# DM1097_HDMI.net
KiCad netlist of a schematic drawn in Altium Designer
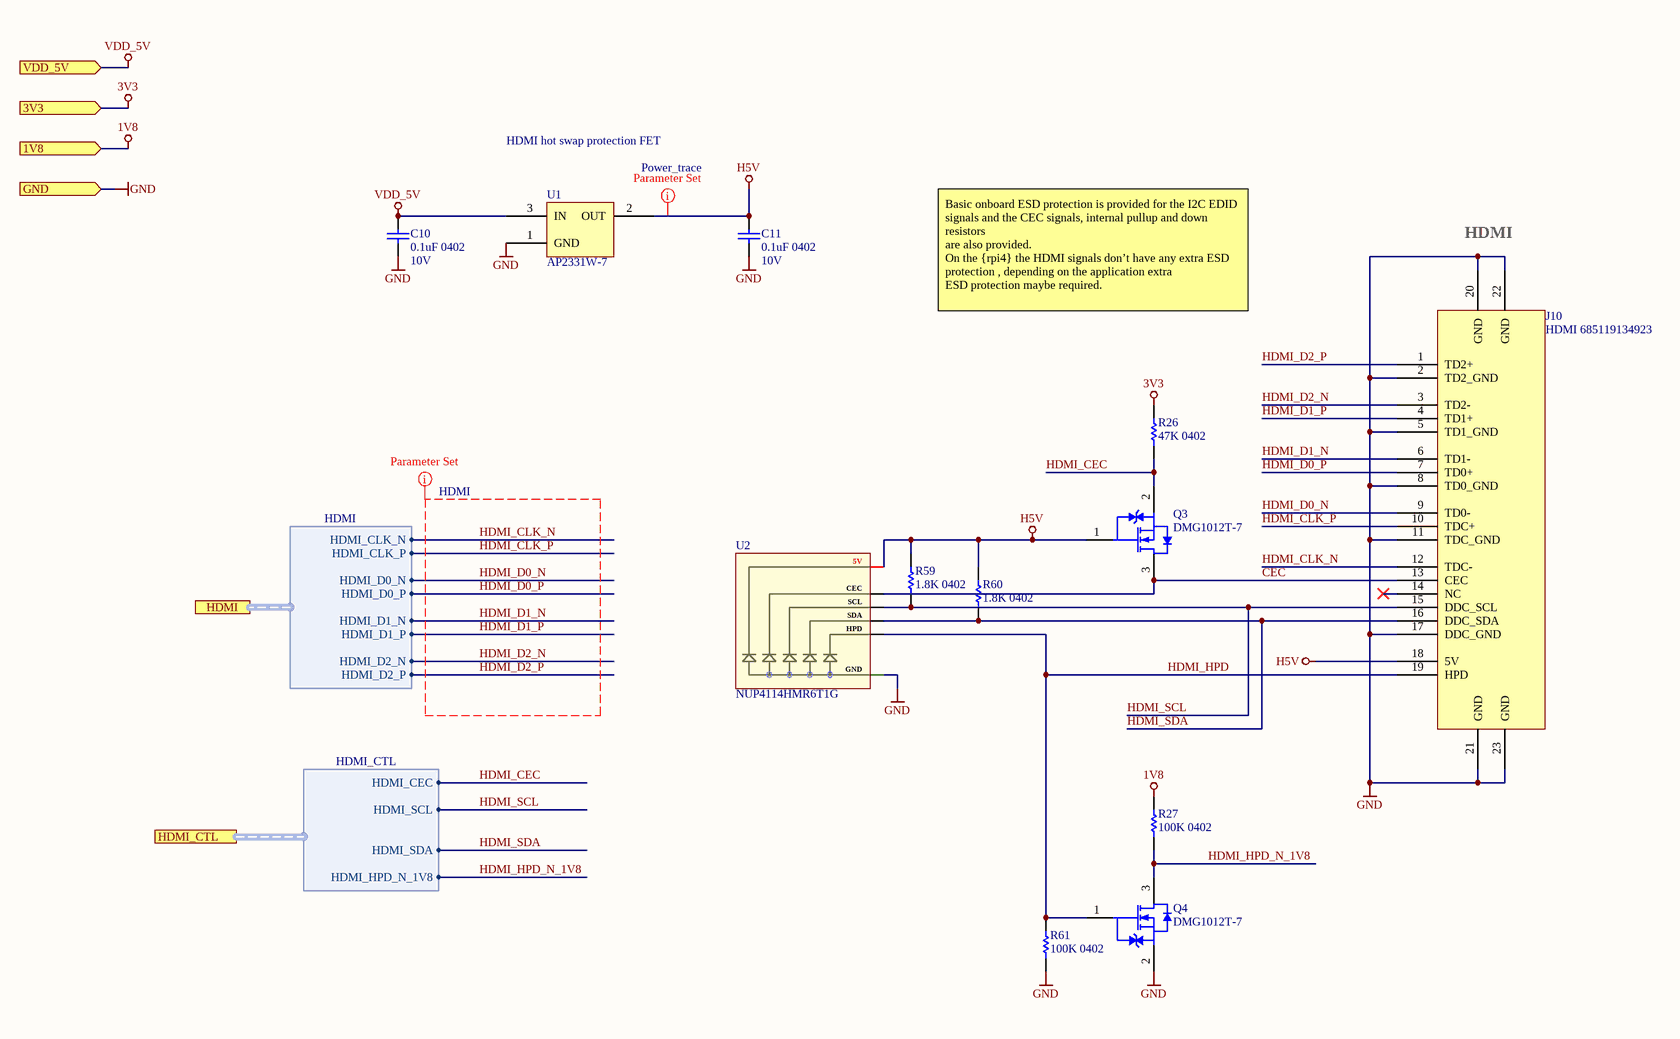
[diagram p0: DM1097_HDMI.SchDoc]

(export (version "E")
  (design (tool "Eeschema 10.0.6"))
  (components
    (comp (ref "C10")
      (value "0.1uF 0402")
      (footprint "CAP_Altium_Vault_Generic:CAPC0402(1005)70_N")
      (description "CAP CER 0.1UF 10V X7R 0402 5%")
      (fields (field (name "TOLERANCE") "5%") (field (name "VOLTAGE RATING") "10V"))
      (libsource (lib "LuxonisMaster") (part "GRM155R71A104JA01D"))
    )
    (comp (ref "C11")
      (value "0.1uF 0402")
      (footprint "CAP_Altium_Vault_Generic:CAPC0402(1005)70_N")
      (description "CAP CER 0.1UF 10V X7R 0402 5%")
      (fields (field (name "TOLERANCE") "5%") (field (name "VOLTAGE RATING") "10V"))
      (libsource (lib "LuxonisMaster") (part "GRM155R71A104JA01D"))
    )
    (comp (ref "J10")
      (value "HDMI 685119134923")
      (footprint "LuxonisMaster:685119134923")
      (description "CONN RCPT HDMI 19POS SMD R/A")
      (libsource (lib "LuxonisMaster") (part "685119134923"))
    )
    (comp (ref "Q3")
      (value "DMG1012T-7")
      (footprint "LuxonisMaster:DMG1012T-7")
      (description "MOSFET N-CH 20V 630MA SOT-523")
      (libsource (lib "LuxonisMaster") (part "DMG1012T-7"))
    )
    (comp (ref "Q4")
      (value "DMG1012T-7")
      (footprint "LuxonisMaster:DMG1012T-7")
      (description "MOSFET N-CH 20V 630MA SOT-523")
      (libsource (lib "LuxonisMaster") (part "DMG1012T-7"))
    )
    (comp (ref "R26")
      (value "47K 0402")
      (footprint "RES_Altium_Vault_Generic:RESC0402(1005)_N")
      (description "RES SMD 47K OHM 1% 1/16W 0402")
      (fields (field (name "TOLERANCE") "1%"))
      (libsource (lib "LuxonisMaster") (part "RC0402FR-0747KL"))
    )
    (comp (ref "R27")
      (value "100K 0402")
      (footprint "RES_Altium_Vault_Generic:RESC0402(1005)_N")
      (description "RES SMD 100K OHM 1% 1/16W 0402")
      (fields (field (name "TOLERANCE") "1%"))
      (libsource (lib "LuxonisMaster") (part "RC0402FR-07100KL"))
    )
    (comp (ref "R59")
      (value "1.8K 0402")
      (footprint "RES_Altium_Vault_Generic:RESC0402(1005)_L")
      (description "RES SMD 1.8K OHM 1% 1/16W 0402")
      (fields (field (name "TOLERANCE") "1%"))
      (libsource (lib "LuxonisMaster") (part "RC0402FR-071K8L"))
    )
    (comp (ref "R60")
      (value "1.8K 0402")
      (footprint "RES_Altium_Vault_Generic:RESC0402(1005)_L")
      (description "RES SMD 1.8K OHM 1% 1/16W 0402")
      (fields (field (name "TOLERANCE") "1%"))
      (libsource (lib "LuxonisMaster") (part "RC0402FR-071K8L"))
    )
    (comp (ref "R61")
      (value "100K 0402")
      (footprint "RES_Altium_Vault_Generic:RESC0402(1005)_N")
      (description "RES SMD 47K OHM 1% 1/16W 0402")
      (fields (field (name "TOLERANCE") "1%"))
      (libsource (lib "LuxonisMaster") (part "RC0402FR-0747KL"))
    )
    (comp (ref "U1")
      (value "AP2331W-7")
      (footprint "LuxonisMaster:AP2331W-7")
      (description "LOAD SWITCH SC59")
      (fields (field (name "VOLTAGE") "5.2V"))
      (libsource (lib "LuxonisMaster") (part "AP2331W-7"))
    )
    (comp (ref "U2")
      (value "NUP4114HMR6T1G")
      (footprint "SOT23-6")
      (description "TVS DIODE 3VWM 9WLCSP")
      (libsource (lib "DM1097_SchLib") (part "NUP4114"))
    )
  )
  (nets
    (net (code "3") (name "/CEC") (class "Default")
      (node (ref "J10") (pin "13") (pinfunction "CEC_13") (pintype "passive"))
      (node (ref "Q3") (pin "3") (pinfunction "3_3") (pintype "passive"))
      (node (ref "U2") (pin "1") (pinfunction "A2_1") (pintype "passive"))
    )
    (net (code "4") (name "/HDMI_CEC") (class "Default")
      (node (ref "Q3") (pin "2") (pinfunction "2_2") (pintype "passive"))
      (node (ref "R26") (pin "1") (pinfunction "1_1") (pintype "passive"))
    )
    (net (code "5") (name "/HDMI_CLK_N") (class "Default")
      (node (ref "J10") (pin "12") (pinfunction "TDC-_12") (pintype "passive"))
    )
    (net (code "6") (name "/HDMI_CLK_P") (class "Default")
      (node (ref "J10") (pin "10") (pinfunction "TDC+_10") (pintype "passive"))
    )
    (net (code "7") (name "/HDMI_D0_N") (class "Default")
      (node (ref "J10") (pin "9") (pinfunction "TD0-_9") (pintype "passive"))
    )
    (net (code "8") (name "/HDMI_D0_P") (class "Default")
      (node (ref "J10") (pin "7") (pinfunction "TD0+_7") (pintype "passive"))
    )
    (net (code "9") (name "/HDMI_D1_N") (class "Default")
      (node (ref "J10") (pin "6") (pinfunction "TD1-_6") (pintype "passive"))
    )
    (net (code "10") (name "/HDMI_D1_P") (class "Default")
      (node (ref "J10") (pin "4") (pinfunction "TD1+_4") (pintype "passive"))
    )
    (net (code "11") (name "/HDMI_D2_N") (class "Default")
      (node (ref "J10") (pin "3") (pinfunction "TD2-_3") (pintype "passive"))
    )
    (net (code "12") (name "/HDMI_D2_P") (class "Default")
      (node (ref "J10") (pin "1") (pinfunction "TD2+_1") (pintype "passive"))
    )
    (net (code "13") (name "/HDMI_HPD") (class "Default")
      (node (ref "J10") (pin "19") (pinfunction "HPD_19") (pintype "passive"))
      (node (ref "Q4") (pin "1") (pinfunction "1_1") (pintype "passive"))
      (node (ref "R61") (pin "2") (pinfunction "2_2") (pintype "passive"))
      (node (ref "U2") (pin "6") (pinfunction "1_6") (pintype "passive"))
    )
    (net (code "14") (name "/HDMI_HPD_N_1V8") (class "Default")
      (node (ref "Q4") (pin "3") (pinfunction "3_3") (pintype "passive"))
      (node (ref "R27") (pin "1") (pinfunction "1_1") (pintype "passive"))
    )
    (net (code "15") (name "/HDMI_SCL") (class "Default")
      (node (ref "J10") (pin "15") (pinfunction "DDC_SCL_15") (pintype "passive"))
      (node (ref "R59") (pin "1") (pinfunction "1_1") (pintype "passive"))
      (node (ref "U2") (pin "3") (pinfunction "A3_3") (pintype "passive"))
    )
    (net (code "16") (name "/HDMI_SDA") (class "Default")
      (node (ref "J10") (pin "16") (pinfunction "DDC_SDA_16") (pintype "passive"))
      (node (ref "R60") (pin "1") (pinfunction "1_1") (pintype "passive"))
      (node (ref "U2") (pin "4") (pinfunction "B3_4") (pintype "passive"))
    )
    (net (code "19") (name "1V8") (class "Default")
      (node (ref "R27") (pin "2") (pinfunction "2_2") (pintype "passive"))
    )
    (net (code "20") (name "3V3") (class "Default")
      (node (ref "R26") (pin "2") (pinfunction "2_2") (pintype "passive"))
    )
    (net (code "21") (name "GND") (class "Default")
      (node (ref "C10") (pin "1") (pinfunction "1_1") (pintype "passive"))
      (node (ref "C11") (pin "1") (pinfunction "1_1") (pintype "passive"))
      (node (ref "J10") (pin "11") (pinfunction "TDC_GND_11") (pintype "passive"))
      (node (ref "J10") (pin "17") (pinfunction "DDC_GND_17") (pintype "passive"))
      (node (ref "J10") (pin "2") (pinfunction "TD2_GND_2") (pintype "passive"))
      (node (ref "J10") (pin "20") (pinfunction "GND_20") (pintype "passive"))
      (node (ref "J10") (pin "21") (pinfunction "GND_21") (pintype "passive"))
      (node (ref "J10") (pin "22") (pinfunction "GND_22") (pintype "passive"))
      (node (ref "J10") (pin "23") (pinfunction "GND_23") (pintype "passive"))
      (node (ref "J10") (pin "5") (pinfunction "TD1_GND_5") (pintype "passive"))
      (node (ref "J10") (pin "8") (pinfunction "TD0_GND_8") (pintype "passive"))
      (node (ref "Q4") (pin "2") (pinfunction "2_2") (pintype "passive"))
      (node (ref "R61") (pin "1") (pinfunction "1_1") (pintype "passive"))
      (node (ref "U1") (pin "1") (pinfunction "GND_1") (pintype "passive"))
      (node (ref "U2") (pin "2") (pinfunction "B2_2") (pintype "passive"))
    )
    (net (code "22") (name "H5V") (class "Default")
      (node (ref "C11") (pin "2") (pinfunction "2_2") (pintype "passive"))
      (node (ref "J10") (pin "18") (pinfunction "5V_18") (pintype "passive"))
      (node (ref "Q3") (pin "1") (pinfunction "1_1") (pintype "passive"))
      (node (ref "R59") (pin "2") (pinfunction "2_2") (pintype "passive"))
      (node (ref "R60") (pin "2") (pinfunction "2_2") (pintype "passive"))
      (node (ref "U1") (pin "2") (pinfunction "OUT_2") (pintype "passive"))
      (node (ref "U2") (pin "5") (pinfunction "A1_5") (pintype "passive"))
    )
    (net (code "23") (name "VDD_5V") (class "Default")
      (node (ref "C10") (pin "2") (pinfunction "2_2") (pintype "passive"))
      (node (ref "U1") (pin "3") (pinfunction "IN_3") (pintype "passive"))
    )
    (net (code "24") (name "unconnected-(J10-NC-Pad14)") (class "Default")
      (node (ref "J10") (pin "14") (pinfunction "NC_14") (pintype "passive+no_connect"))
    )
  )
)
